# V2_0_2_Signal_Relay_Switch.net
KiCad netlist of a schematic drawn in EasyEDA Pro
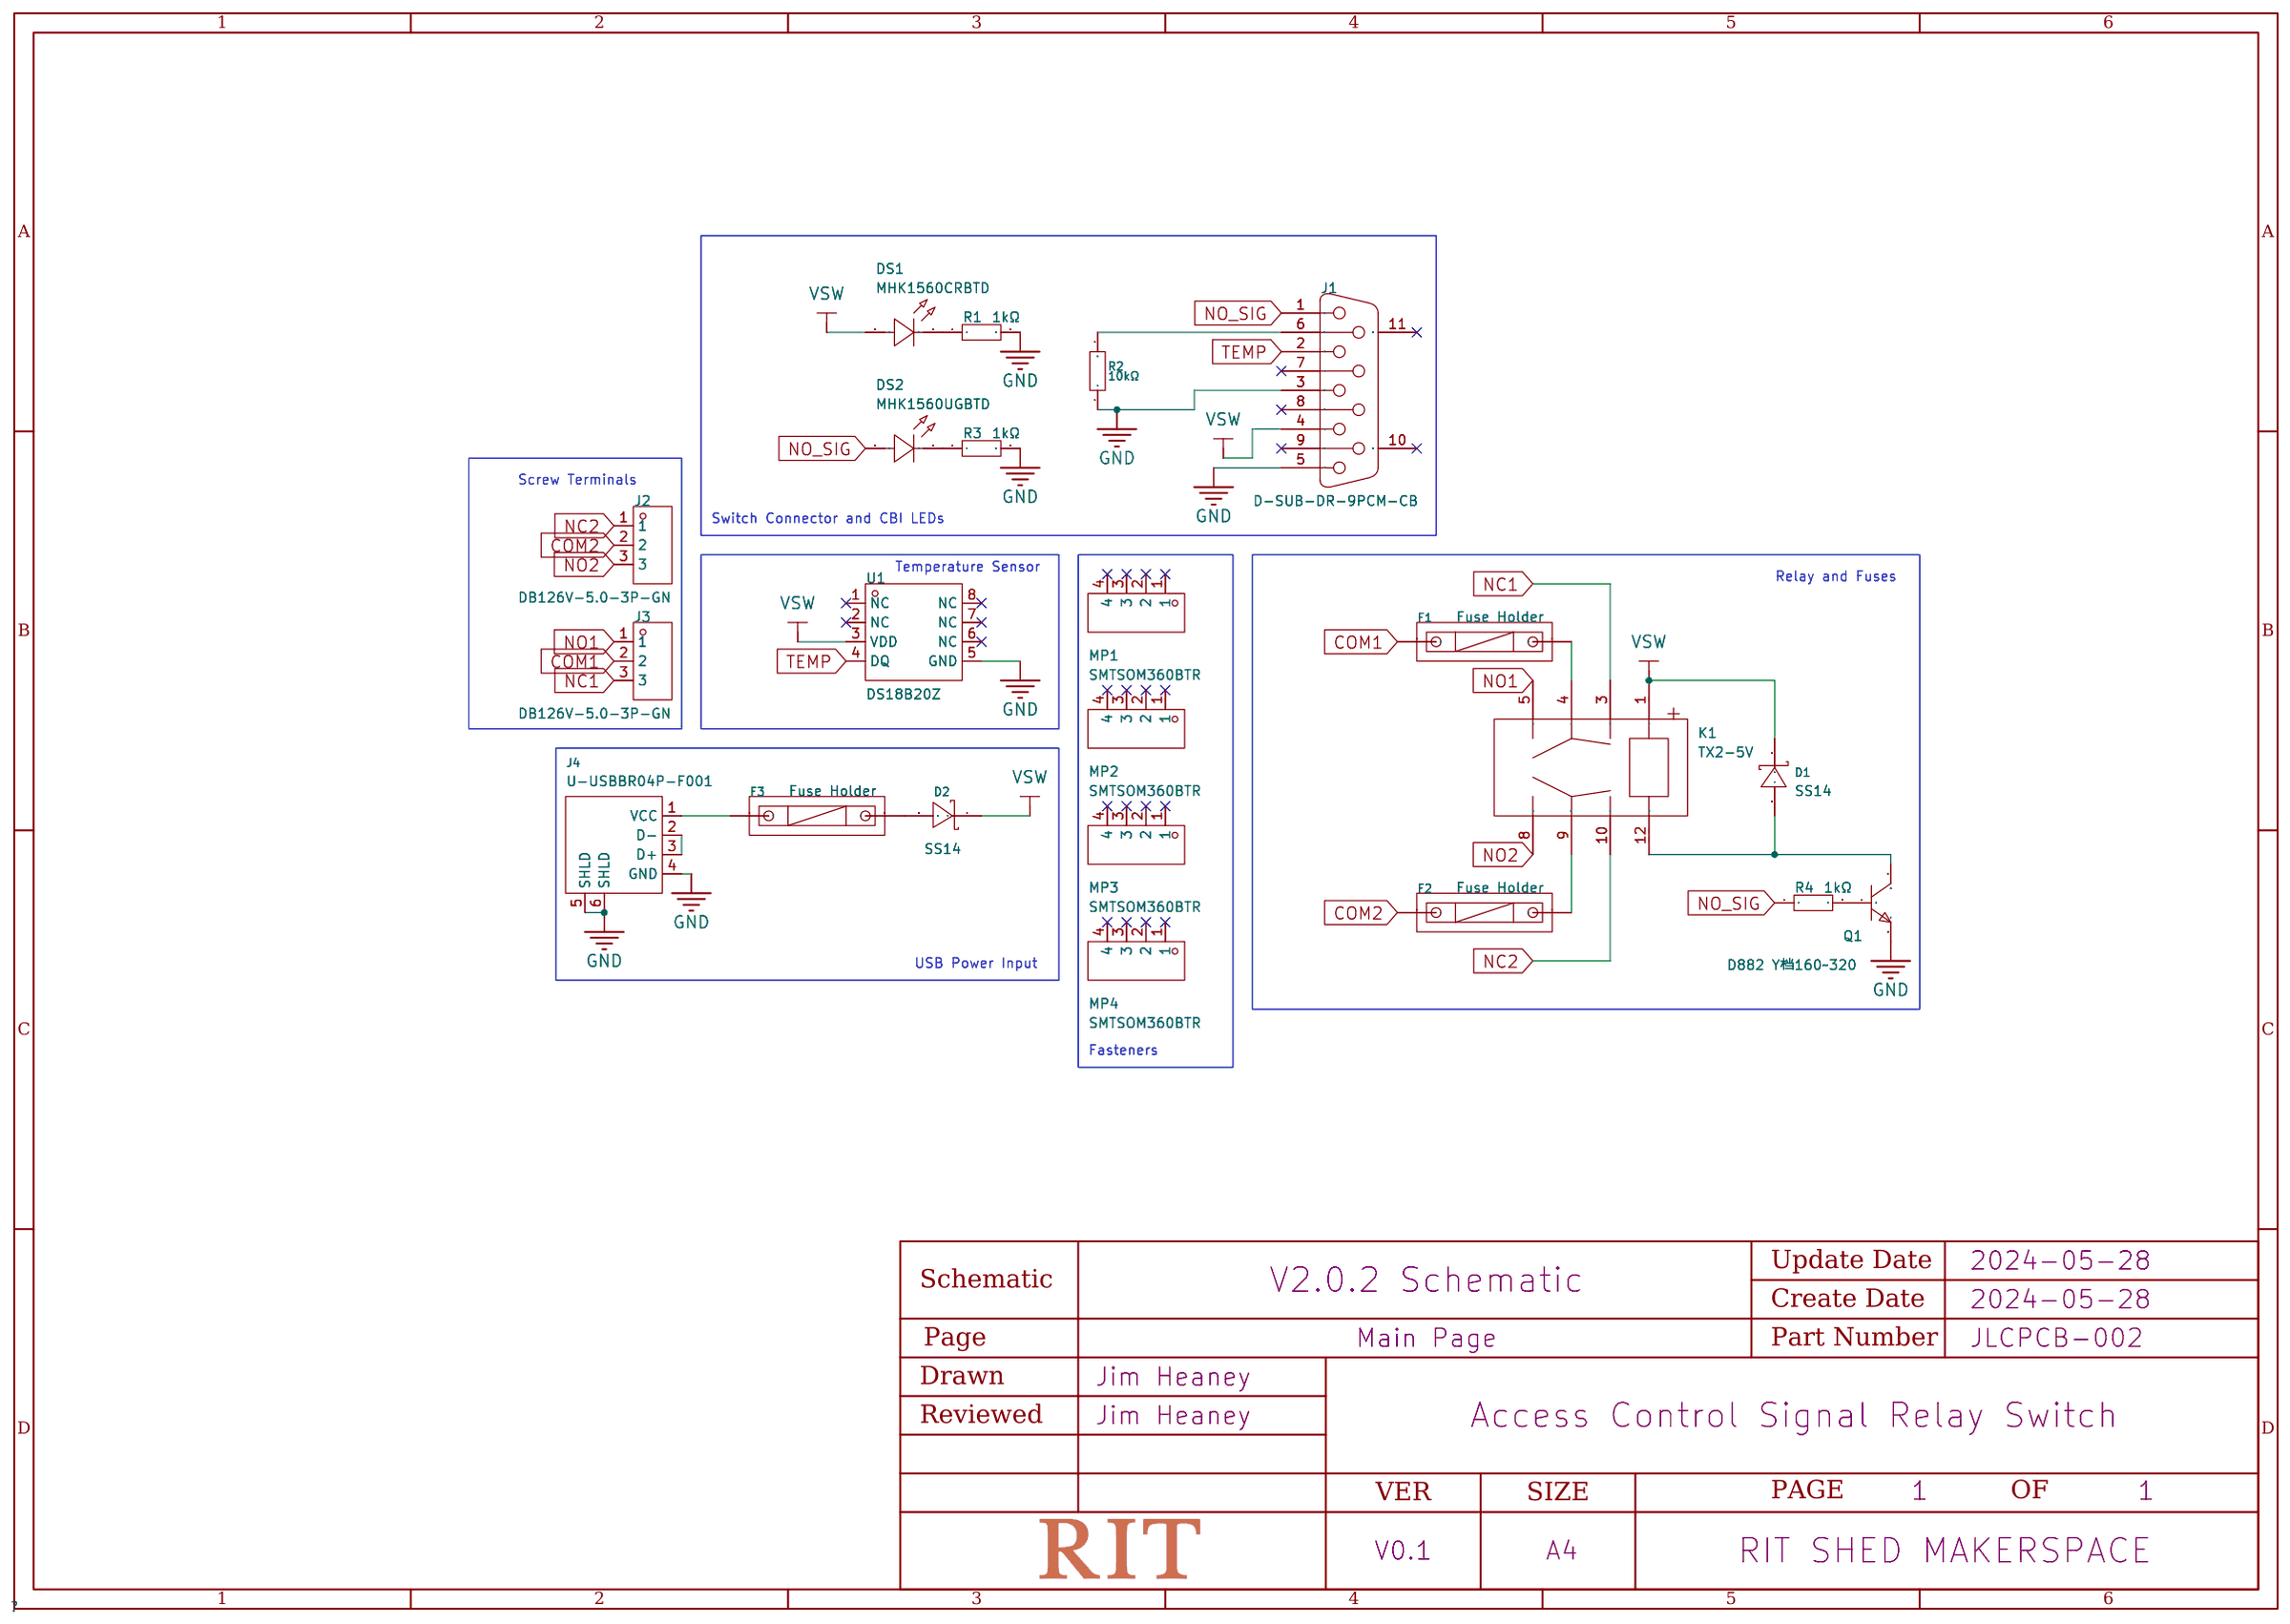
[diagram p0: schematic sheet]

(export (version "E")
  (design (tool "Eeschema 10.0.6"))
  (components
    (comp (ref "D1")
      (value "SS14")
      (footprint "easyedapro:SMA_L4.2-W2.6-LS5.3-RD")
      (fields (field (name "Manufacturer") "MDD"))
      (libsource (lib "easyedapro") (part "SS14"))
    )
    (comp (ref "D2")
      (value "SS14")
      (footprint "easyedapro:SMA_L4.2-W2.6-LS5.3-RD")
      (fields (field (name "Manufacturer") "MDD"))
      (libsource (lib "easyedapro") (part "SS14"))
    )
    (comp (ref "DS1")
      (value "MHK1560CRBTD")
      (footprint "easyedapro:LED-TH_MHK1560UGBTD")
      (fields (field (name "Manufacturer") "MEIHUA(美华)"))
      (libsource (lib "easyedapro") (part "MHK1560CGBTD"))
    )
    (comp (ref "DS2")
      (value "MHK1560UGBTD")
      (footprint "easyedapro:LED-TH_MHK1560UGBTD")
      (fields (field (name "Manufacturer") "MEIHUA(美华)"))
      (libsource (lib "easyedapro") (part "MHK1560UGBTD"))
    )
    (comp (ref "F1")
      (value "Fuse Holder")
      (footprint "easyedapro:FUSE-TH_L24.5-W9.8-P22.5")
      (description "Fuseholder Type:- Fuse Type:- Fuse Size:-")
      (fields (field (name "Manufacturer Part") "保险丝透明座") (field (name "Manufacturer") "xcfuse(旭程)"))
      (libsource (lib "easyedapro") (part "Fuse transparent seat"))
    )
    (comp (ref "F2")
      (value "Fuse Holder")
      (footprint "easyedapro:FUSE-TH_L24.5-W9.8-P22.5")
      (description "Fuseholder Type:- Fuse Type:- Fuse Size:-")
      (fields (field (name "Manufacturer Part") "保险丝透明座") (field (name "Manufacturer") "xcfuse(旭程)"))
      (libsource (lib "easyedapro") (part "Fuse transparent seat"))
    )
    (comp (ref "F3")
      (value "Fuse Holder")
      (footprint "easyedapro:FUSE-TH_L24.5-W9.8-P22.5")
      (description "Fuseholder Type:- Fuse Type:- Fuse Size:-")
      (fields (field (name "Manufacturer Part") "保险丝透明座") (field (name "Manufacturer") "xcfuse(旭程)"))
      (libsource (lib "easyedapro") (part "Fuse transparent seat"))
    )
    (comp (ref "J1")
      (value "D-SUB-DR-9PCM-CB")
      (footprint "easyedapro:DB9-TH_ID09S33E4GV00LF")
      (fields (field (name "Manufacturer") "XUNPU(讯普)"))
      (libsource (lib "easyedapro") (part "D-SUB-DR-9PCM-CB"))
    )
    (comp (ref "J2")
      (value "DB126V-5.0-3P-GN")
      (footprint "easyedapro:CONN-TH_3P-P5.00_DB126V-5.0-3P")
      (fields (field (name "Manufacturer") "DORABO(地博电气)"))
      (libsource (lib "easyedapro") (part "DB126V-5.0-3P"))
    )
    (comp (ref "J3")
      (value "DB126V-5.0-3P-GN")
      (footprint "easyedapro:CONN-TH_3P-P5.00_DB126V-5.0-3P")
      (fields (field (name "Manufacturer") "DORABO(地博电气)"))
      (libsource (lib "easyedapro") (part "DB126V-5.0-3P"))
    )
    (comp (ref "J4")
      (value "U-USBBR04P-F001")
      (footprint "easyedapro:USB-B-TH_U241-041N-1BR85-1")
      (fields (field (name "Manufacturer") "Ckmtw(灿科盟)"))
      (libsource (lib "easyedapro") (part "U-USBBR04P-F001"))
    )
    (comp (ref "K1")
      (value "TX2-5V")
      (footprint "easyedapro:RELAY-TH_TX2-3V")
      (fields (field (name "Manufacturer") "PANASONIC(松下)"))
      (libsource (lib "easyedapro") (part "TX2-5V"))
    )
    (comp (ref "MP1")
      (value "SMTSOM360BTR")
      (footprint "easyedapro:SMD_BD5.6-D4.1")
      (fields (field (name "Manufacturer") "YIYUAN(怡远)"))
      (libsource (lib "easyedapro") (part "SMTSOM360BTR"))
    )
    (comp (ref "MP2")
      (value "SMTSOM360BTR")
      (footprint "easyedapro:SMD_BD5.6-D4.1")
      (fields (field (name "Manufacturer") "YIYUAN(怡远)"))
      (libsource (lib "easyedapro") (part "SMTSOM360BTR"))
    )
    (comp (ref "MP3")
      (value "SMTSOM360BTR")
      (footprint "easyedapro:SMD_BD5.6-D4.1")
      (fields (field (name "Manufacturer") "YIYUAN(怡远)"))
      (libsource (lib "easyedapro") (part "SMTSOM360BTR"))
    )
    (comp (ref "MP4")
      (value "SMTSOM360BTR")
      (footprint "easyedapro:SMD_BD5.6-D4.1")
      (fields (field (name "Manufacturer") "YIYUAN(怡远)"))
      (libsource (lib "easyedapro") (part "SMTSOM360BTR"))
    )
    (comp (ref "Q1")
      (value "D882 Y档160~320")
      (footprint "easyedapro:SOT-89-3_L4.5-W2.5-P1.50-LS4.2-BR")
      (fields (field (name "Manufacturer") "CJ(江苏长电/长晶)"))
      (libsource (lib "easyedapro") (part "D882_C9634"))
    )
    (comp (ref "R1")
      (value "1kΩ")
      (footprint "easyedapro:R0805")
      (fields
        (field (name "Manufacturer Part") "0805W8F1001T5E")
        (field (name "Manufacturer") "UNI-ROYAL(厚声)")
      )
      (libsource (lib "easyedapro") (part "0805W8F1001T5E"))
    )
    (comp (ref "R2")
      (value "10kΩ")
      (footprint "easyedapro:R0805")
      (fields
        (field (name "Manufacturer Part") "0805W8F1002T5E")
        (field (name "Manufacturer") "UNI-ROYAL(厚声)")
      )
      (libsource (lib "easyedapro") (part "0805W8F1002T5E"))
    )
    (comp (ref "R3")
      (value "1kΩ")
      (footprint "easyedapro:R0805")
      (fields
        (field (name "Manufacturer Part") "0805W8F1001T5E")
        (field (name "Manufacturer") "UNI-ROYAL(厚声)")
      )
      (libsource (lib "easyedapro") (part "0805W8F1001T5E"))
    )
    (comp (ref "R4")
      (value "1kΩ")
      (footprint "easyedapro:R0805")
      (fields
        (field (name "Manufacturer Part") "0805W8F1001T5E")
        (field (name "Manufacturer") "UNI-ROYAL(厚声)")
      )
      (libsource (lib "easyedapro") (part "0805W8F1001T5E"))
    )
    (comp (ref "U1")
      (value "DS18B20Z")
      (footprint "easyedapro:SOP-8_L4.9-W3.9-P1.27-LS6.0-BL")
      (description "Resolution:±0.4°C Resolution:±0.4°C Supply Voltage:2.5V~5.5V Supply Voltage:2.5V~5.5V")
      (fields (field (name "Manufacturer") "UMW(友台半导体)"))
      (libsource (lib "easyedapro") (part "DS18B20Z"))
    )
  )
  (nets
    (net (code "1") (name "COM1") (class "Default")
      (node (ref "F1") (pin "1") (pinfunction "1_1") (pintype "input"))
      (node (ref "J3") (pin "2") (pinfunction "2_2") (pintype "unspecified"))
    )
    (net (code "2") (name "COM2") (class "Default")
      (node (ref "F2") (pin "1") (pinfunction "1_1") (pintype "input"))
      (node (ref "J2") (pin "2") (pinfunction "2_2") (pintype "unspecified"))
    )
    (net (code "3") (name "GND") (class "Default")
      (node (ref "J1") (pin "3") (pinfunction "3_3") (pintype "input"))
      (node (ref "J1") (pin "5") (pinfunction "5_5") (pintype "input"))
      (node (ref "J4") (pin "4") (pinfunction "GND_4") (pintype "input"))
      (node (ref "J4") (pin "5") (pinfunction "SHLD_5") (pintype "input"))
      (node (ref "J4") (pin "6") (pinfunction "SHLD_6") (pintype "input"))
      (node (ref "Q1") (pin "3") (pinfunction "E_3") (pintype "input"))
      (node (ref "R1") (pin "2") (pinfunction "2_2") (pintype "input"))
      (node (ref "R2") (pin "1") (pinfunction "1_1") (pintype "input"))
      (node (ref "R3") (pin "2") (pinfunction "2_2") (pintype "input"))
      (node (ref "U1") (pin "5") (pinfunction "GND_5") (pintype "unspecified"))
    )
    (net (code "4") (name "NC1") (class "Default")
      (node (ref "J3") (pin "3") (pinfunction "3_3") (pintype "unspecified"))
      (node (ref "K1") (pin "3") (pinfunction "3_3") (pintype "unspecified"))
    )
    (net (code "5") (name "NC2") (class "Default")
      (node (ref "J2") (pin "1") (pinfunction "1_1") (pintype "unspecified"))
      (node (ref "K1") (pin "10") (pinfunction "10_10") (pintype "unspecified"))
    )
    (net (code "6") (name "NO1") (class "Default")
      (node (ref "J3") (pin "1") (pinfunction "1_1") (pintype "unspecified"))
      (node (ref "K1") (pin "5") (pinfunction "5_5") (pintype "unspecified"))
    )
    (net (code "7") (name "NO2") (class "Default")
      (node (ref "J2") (pin "3") (pinfunction "3_3") (pintype "unspecified"))
      (node (ref "K1") (pin "8") (pinfunction "8_8") (pintype "unspecified"))
    )
    (net (code "8") (name "NO_SIG") (class "Default")
      (node (ref "DS2") (pin "2") (pinfunction "A_2") (pintype "unspecified"))
      (node (ref "J1") (pin "1") (pinfunction "1_1") (pintype "input"))
      (node (ref "R4") (pin "1") (pinfunction "1_1") (pintype "input"))
    )
    (net (code "9") (name "Net-(D1-A)") (class "Default")
      (node (ref "D1") (pin "2") (pinfunction "A_2") (pintype "unspecified"))
      (node (ref "K1") (pin "12") (pinfunction "12_12") (pintype "unspecified"))
      (node (ref "Q1") (pin "2") (pinfunction "C_2") (pintype "input"))
    )
    (net (code "10") (name "Net-(D2-A)") (class "Default")
      (node (ref "D2") (pin "2") (pinfunction "A_2") (pintype "unspecified"))
      (node (ref "F3") (pin "2") (pinfunction "2_2") (pintype "input"))
    )
    (net (code "11") (name "Net-(DS1-K)") (class "Default")
      (node (ref "DS1") (pin "1") (pinfunction "K_1") (pintype "unspecified"))
      (node (ref "R1") (pin "1") (pinfunction "1_1") (pintype "input"))
    )
    (net (code "12") (name "Net-(DS2-K)") (class "Default")
      (node (ref "DS2") (pin "1") (pinfunction "K_1") (pintype "unspecified"))
      (node (ref "R3") (pin "1") (pinfunction "1_1") (pintype "input"))
    )
    (net (code "13") (name "Net-(F1-Pad2)") (class "Default")
      (node (ref "F1") (pin "2") (pinfunction "2_2") (pintype "input"))
      (node (ref "K1") (pin "4") (pinfunction "4_4") (pintype "unspecified"))
    )
    (net (code "14") (name "Net-(F2-Pad2)") (class "Default")
      (node (ref "F2") (pin "2") (pinfunction "2_2") (pintype "input"))
      (node (ref "K1") (pin "9") (pinfunction "9_9") (pintype "unspecified"))
    )
    (net (code "15") (name "Net-(J1-Pad6)") (class "Default")
      (node (ref "J1") (pin "6") (pinfunction "6_6") (pintype "input"))
      (node (ref "R2") (pin "2") (pinfunction "2_2") (pintype "input"))
    )
    (net (code "16") (name "Net-(J4-D+)") (class "Default")
      (node (ref "J4") (pin "2") (pinfunction "D-_2") (pintype "input"))
      (node (ref "J4") (pin "3") (pinfunction "D+_3") (pintype "input"))
    )
    (net (code "17") (name "Net-(J4-VCC)") (class "Default")
      (node (ref "F3") (pin "1") (pinfunction "1_1") (pintype "input"))
      (node (ref "J4") (pin "1") (pinfunction "VCC_1") (pintype "input"))
    )
    (net (code "18") (name "Net-(Q1-B)") (class "Default")
      (node (ref "Q1") (pin "1") (pinfunction "B_1") (pintype "input"))
      (node (ref "R4") (pin "2") (pinfunction "2_2") (pintype "input"))
    )
    (net (code "19") (name "TEMP") (class "Default")
      (node (ref "J1") (pin "2") (pinfunction "2_2") (pintype "input"))
      (node (ref "U1") (pin "4") (pinfunction "DQ_4") (pintype "unspecified"))
    )
    (net (code "20") (name "VSW") (class "Default")
      (node (ref "D1") (pin "1") (pinfunction "K_1") (pintype "unspecified"))
      (node (ref "D2") (pin "1") (pinfunction "K_1") (pintype "unspecified"))
      (node (ref "DS1") (pin "2") (pinfunction "A_2") (pintype "unspecified"))
      (node (ref "J1") (pin "4") (pinfunction "4_4") (pintype "input"))
      (node (ref "K1") (pin "1") (pinfunction "1_1") (pintype "unspecified"))
      (node (ref "U1") (pin "3") (pinfunction "VDD_3") (pintype "unspecified"))
    )
    (net (code "21") (name "unconnected-(J1-MH1-Pad10)") (class "Default")
      (node (ref "J1") (pin "10") (pinfunction "MH1_10") (pintype "input+no_connect"))
    )
    (net (code "22") (name "unconnected-(J1-MH2-Pad11)") (class "Default")
      (node (ref "J1") (pin "11") (pinfunction "MH2_11") (pintype "input+no_connect"))
    )
    (net (code "23") (name "unconnected-(J1-Pad7)") (class "Default")
      (node (ref "J1") (pin "7") (pinfunction "7_7") (pintype "input+no_connect"))
    )
    (net (code "24") (name "unconnected-(J1-Pad8)") (class "Default")
      (node (ref "J1") (pin "8") (pinfunction "8_8") (pintype "input+no_connect"))
    )
    (net (code "25") (name "unconnected-(J1-Pad9)") (class "Default")
      (node (ref "J1") (pin "9") (pinfunction "9_9") (pintype "input+no_connect"))
    )
    (net (code "26") (name "unconnected-(MP1-Pad1)") (class "Default")
      (node (ref "MP1") (pin "1") (pinfunction "1_1") (pintype "unspecified+no_connect"))
    )
    (net (code "27") (name "unconnected-(MP1-Pad2)") (class "Default")
      (node (ref "MP1") (pin "2") (pinfunction "2_2") (pintype "unspecified+no_connect"))
    )
    (net (code "28") (name "unconnected-(MP1-Pad3)") (class "Default")
      (node (ref "MP1") (pin "3") (pinfunction "3_3") (pintype "unspecified+no_connect"))
    )
    (net (code "29") (name "unconnected-(MP1-Pad4)") (class "Default")
      (node (ref "MP1") (pin "4") (pinfunction "4_4") (pintype "unspecified+no_connect"))
    )
    (net (code "30") (name "unconnected-(MP2-Pad1)") (class "Default")
      (node (ref "MP2") (pin "1") (pinfunction "1_1") (pintype "unspecified+no_connect"))
    )
    (net (code "31") (name "unconnected-(MP2-Pad2)") (class "Default")
      (node (ref "MP2") (pin "2") (pinfunction "2_2") (pintype "unspecified+no_connect"))
    )
    (net (code "32") (name "unconnected-(MP2-Pad3)") (class "Default")
      (node (ref "MP2") (pin "3") (pinfunction "3_3") (pintype "unspecified+no_connect"))
    )
    (net (code "33") (name "unconnected-(MP2-Pad4)") (class "Default")
      (node (ref "MP2") (pin "4") (pinfunction "4_4") (pintype "unspecified+no_connect"))
    )
    (net (code "34") (name "unconnected-(MP3-Pad1)") (class "Default")
      (node (ref "MP3") (pin "1") (pinfunction "1_1") (pintype "unspecified+no_connect"))
    )
    (net (code "35") (name "unconnected-(MP3-Pad2)") (class "Default")
      (node (ref "MP3") (pin "2") (pinfunction "2_2") (pintype "unspecified+no_connect"))
    )
    (net (code "36") (name "unconnected-(MP3-Pad3)") (class "Default")
      (node (ref "MP3") (pin "3") (pinfunction "3_3") (pintype "unspecified+no_connect"))
    )
    (net (code "37") (name "unconnected-(MP3-Pad4)") (class "Default")
      (node (ref "MP3") (pin "4") (pinfunction "4_4") (pintype "unspecified+no_connect"))
    )
    (net (code "38") (name "unconnected-(MP4-Pad1)") (class "Default")
      (node (ref "MP4") (pin "1") (pinfunction "1_1") (pintype "unspecified+no_connect"))
    )
    (net (code "39") (name "unconnected-(MP4-Pad2)") (class "Default")
      (node (ref "MP4") (pin "2") (pinfunction "2_2") (pintype "unspecified+no_connect"))
    )
    (net (code "40") (name "unconnected-(MP4-Pad3)") (class "Default")
      (node (ref "MP4") (pin "3") (pinfunction "3_3") (pintype "unspecified+no_connect"))
    )
    (net (code "41") (name "unconnected-(MP4-Pad4)") (class "Default")
      (node (ref "MP4") (pin "4") (pinfunction "4_4") (pintype "unspecified+no_connect"))
    )
    (net (code "42") (name "unconnected-(U1-NC-Pad1)") (class "Default")
      (node (ref "U1") (pin "1") (pinfunction "NC_1") (pintype "unspecified+no_connect"))
    )
    (net (code "43") (name "unconnected-(U1-NC-Pad2)") (class "Default")
      (node (ref "U1") (pin "2") (pinfunction "NC_2") (pintype "unspecified+no_connect"))
    )
    (net (code "44") (name "unconnected-(U1-NC-Pad6)") (class "Default")
      (node (ref "U1") (pin "6") (pinfunction "NC_6") (pintype "unspecified+no_connect"))
    )
    (net (code "45") (name "unconnected-(U1-NC-Pad7)") (class "Default")
      (node (ref "U1") (pin "7") (pinfunction "NC_7") (pintype "unspecified+no_connect"))
    )
    (net (code "46") (name "unconnected-(U1-NC-Pad8)") (class "Default")
      (node (ref "U1") (pin "8") (pinfunction "NC_8") (pintype "unspecified+no_connect"))
    )
  )
)
